# 01_Power.net
KiCad netlist of a schematic drawn in Altium Designer
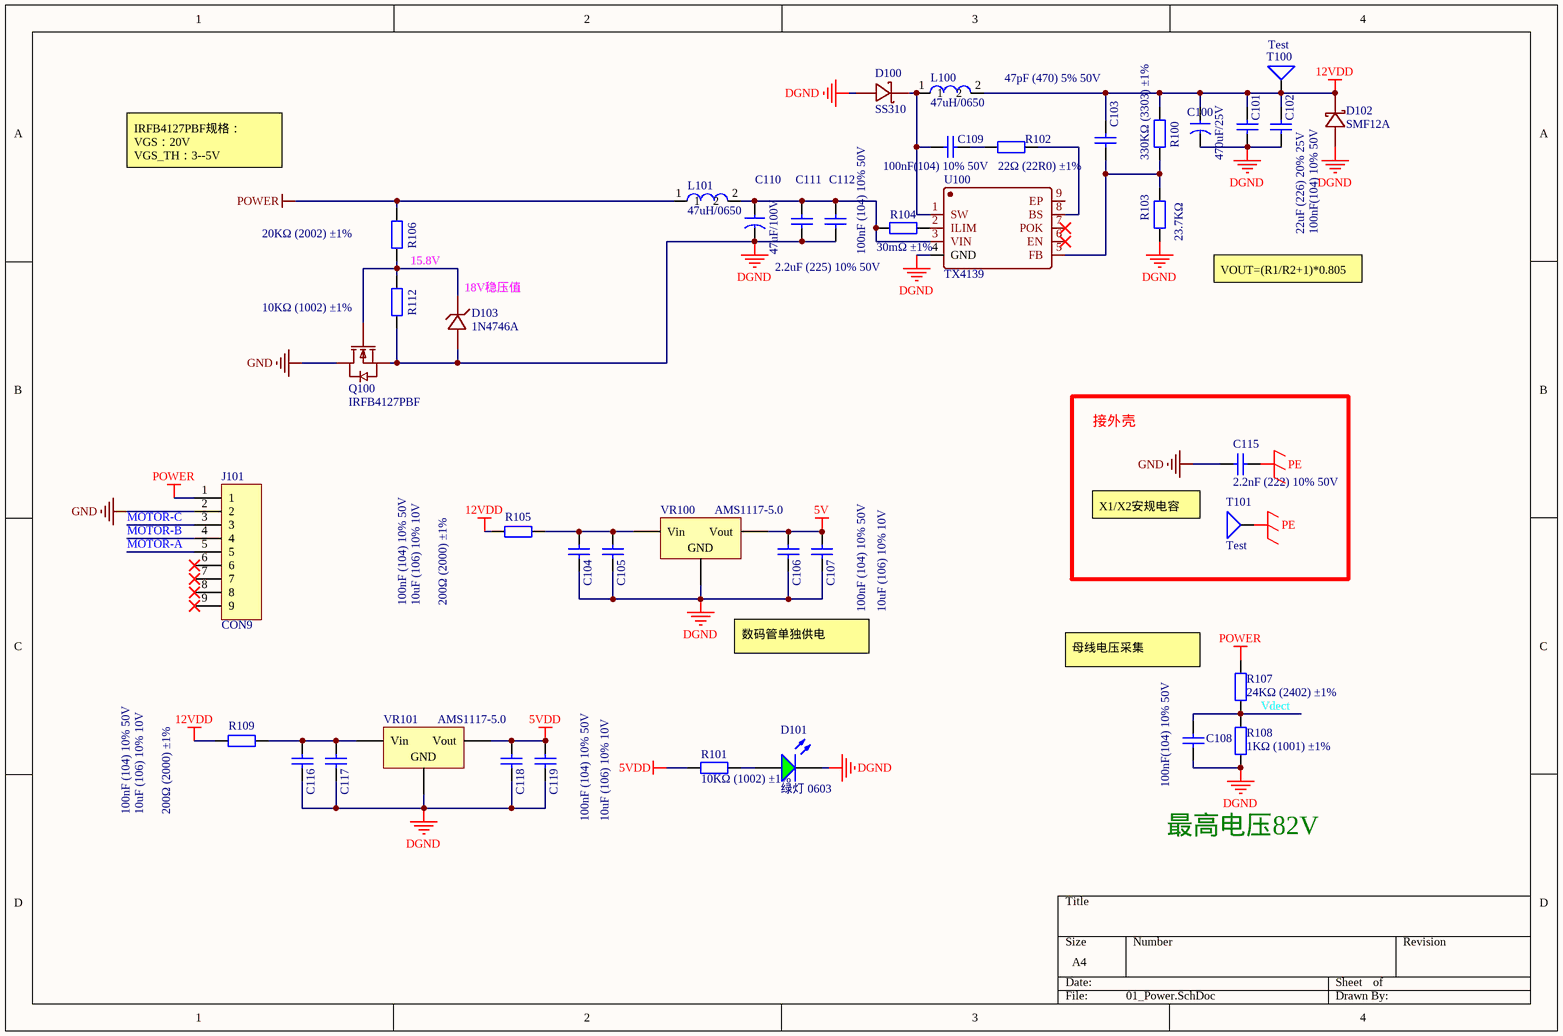
[diagram p0: 01_Power.SchDoc]

(export (version "E")
  (design (tool "Eeschema 10.0.6"))
  (components
    (comp (ref "C100")
      (value "470uF/25V")
      (footprint "47UF/100V")
      (libsource (lib "RayPCB20210502") (part "CapSMT220u_16V"))
    )
    (comp (ref "C101")
      (value "22uF (226) 20% 25V")
      (footprint "0805_C")
      (description "贴片电容")
      (libsource (lib "Miscellaneous Devices LC") (part "0805 22uF (226) 20% 25V"))
    )
    (comp (ref "C102")
      (value "100nF(104) 10% 50V")
      (footprint "0805_C")
      (description "贴片电容")
      (libsource (lib "Miscellaneous Devices LC") (part "0805 100nF(104) 10% 50V"))
    )
    (comp (ref "C103")
      (value "47pF (470) 5% 50V")
      (footprint "0805_C")
      (description "贴片电容")
      (libsource (lib "Miscellaneous Devices LC") (part "0805 47pF (470) 5% 50V"))
    )
    (comp (ref "C104")
      (value "100nF (104) 10% 50V")
      (footprint "0603_C")
      (description "贴片电容")
      (libsource (lib "Miscellaneous Devices LC") (part "0603 100nF (104) 10% 50V"))
    )
    (comp (ref "C105")
      (value "10uF (106) 10% 10V")
      (footprint "0603_C")
      (description "贴片电容")
      (libsource (lib "Miscellaneous Devices LC") (part "0603 10uF (106) 10% 10V"))
    )
    (comp (ref "C106")
      (value "100nF (104) 10% 50V")
      (footprint "0603_C")
      (description "贴片电容")
      (libsource (lib "Miscellaneous Devices LC") (part "0603 100nF (104) 10% 50V"))
    )
    (comp (ref "C107")
      (value "10uF (106) 10% 10V")
      (footprint "0603_C")
      (description "贴片电容")
      (libsource (lib "Miscellaneous Devices LC") (part "0603 10uF (106) 10% 10V"))
    )
    (comp (ref "C108")
      (value "100nF(104) 10% 50V")
      (footprint "0805_C")
      (description "贴片电容")
      (libsource (lib "Miscellaneous Devices LC") (part "0805 100nF(104) 10% 50V"))
    )
    (comp (ref "C109")
      (value "100nF(104) 10% 50V")
      (footprint "0805_C")
      (description "贴片电容")
      (libsource (lib "Miscellaneous Devices LC") (part "0805 100nF(104) 10% 50V"))
    )
    (comp (ref "C110")
      (value "47uF/100V")
      (footprint "47UF/100V")
      (libsource (lib "RayPCB20210502") (part "CapSMT220u_16V"))
    )
    (comp (ref "C111")
      (value "2.2uF (225) 10% 50V")
      (footprint "1206_C")
      (description "贴片电容")
      (libsource (lib "Miscellaneous Devices LC") (part "1206 2.2uF (225) 10% 50V"))
    )
    (comp (ref "C112")
      (value "100nF (104) 10% 50V")
      (footprint "1206_C")
      (description "贴片电容")
      (libsource (lib "Miscellaneous Devices LC") (part "1206 100nF (104) 10% 50V"))
    )
    (comp (ref "C115")
      (value "2.2nF (222) 10% 50V")
      (footprint "X1/Y1 500V")
      (description "贴片电容")
      (libsource (lib "Miscellaneous Devices LC") (part "0603 2.2nF (222) 10% 50V"))
    )
    (comp (ref "C116")
      (value "100nF (104) 10% 50V")
      (footprint "0603_C")
      (description "贴片电容")
      (libsource (lib "Miscellaneous Devices LC") (part "0603 100nF (104) 10% 50V"))
    )
    (comp (ref "C117")
      (value "10uF (106) 10% 10V")
      (footprint "0603_C")
      (description "贴片电容")
      (libsource (lib "Miscellaneous Devices LC") (part "0603 10uF (106) 10% 10V"))
    )
    (comp (ref "C118")
      (value "100nF (104) 10% 50V")
      (footprint "0603_C")
      (description "贴片电容")
      (libsource (lib "Miscellaneous Devices LC") (part "0603 100nF (104) 10% 50V"))
    )
    (comp (ref "C119")
      (value "10uF (106) 10% 10V")
      (footprint "0603_C")
      (description "贴片电容")
      (libsource (lib "Miscellaneous Devices LC") (part "0603 10uF (106) 10% 10V"))
    )
    (comp (ref "D100") (value "SS310") (footprint "SS310") (libsource (lib "Schlibv2") (part "SS310")))
    (comp (ref "D101")
      (value "绿灯 0603")
      (footprint "0603_LED_S1")
      (description "发光二极管")
      (libsource (lib "Miscellaneous Devices LC") (part "0603 绿灯"))
    )
    (comp (ref "D102")
      (value "SMF12A")
      (footprint "SMF12A - duplicate")
      (libsource (lib "RayPCB20210502") (part "SMF12A"))
    )
    (comp (ref "D103") (value "1N4746A") (footprint "1N4746A") (libsource (lib "Schlibv2") (part "1N4746A")))
    (comp (ref "J101")
      (value "CON9")
      (footprint "CON9 9.5mm")
      (libsource (lib "RayPCB20210502") (part "CON9"))
    )
    (comp (ref "L100")
      (value "47uH/0650")
      (footprint "0650_47uH")
      (libsource (lib "RayPCB20210502") (part "Inductor"))
    )
    (comp (ref "L101")
      (value "47uH/0650")
      (footprint "0650_47uH")
      (libsource (lib "RayPCB20210502") (part "Inductor"))
    )
    (comp (ref "Q100")
      (value "IRFB4127PBF")
      (footprint "IRFB4127")
      (libsource (lib "RayPCB20210502") (part "IRFB4127PBF"))
    )
    (comp (ref "R100")
      (value "330KΩ (3303) ±1%")
      (footprint "0805_R")
      (description "贴片电阻")
      (libsource (lib "Miscellaneous Devices LC") (part "0805 330KΩ (3303) 1%"))
    )
    (comp (ref "R101")
      (value "10KΩ (1002) ±1%")
      (footprint "0603_R")
      (description "贴片电阻")
      (libsource (lib "Miscellaneous Devices LC") (part "0603 10KΩ (1002) 1%"))
    )
    (comp (ref "R102")
      (value "22Ω (22R0) ±1%")
      (footprint "0805_R")
      (description "贴片电阻")
      (libsource (lib "") (part "0805 22Ω (22R0) 1%_1"))
    )
    (comp (ref "R103")
      (value "23.7KΩ")
      (footprint "0805_R")
      (description "贴片电阻")
      (libsource (lib "Miscellaneous Devices LC") (part "0805 22Ω (22R0) 1%"))
    )
    (comp (ref "R104")
      (value "30mΩ ±1%")
      (footprint "0603_R")
      (description "贴片电阻")
      (libsource (lib "Miscellaneous Devices LC") (part "0603 100KΩ (1003) 1%"))
    )
    (comp (ref "R105")
      (value "200Ω (2000) ±1%")
      (footprint "1206_R")
      (description "贴片电阻")
      (libsource (lib "Miscellaneous Devices LC") (part "1206 300Ω (3000) 1%"))
    )
    (comp (ref "R106")
      (value "20KΩ (2002) ±1%")
      (footprint "0805_R")
      (description "贴片电阻")
      (libsource (lib "Miscellaneous Devices LC") (part "0805 20KΩ (2002) 1%"))
    )
    (comp (ref "R107")
      (value "24KΩ (2402) ±1%")
      (footprint "1206_R")
      (description "贴片电阻")
      (libsource (lib "Miscellaneous Devices LC") (part "1206 0Ω (0R0) 1%"))
    )
    (comp (ref "R108")
      (value "1KΩ (1001) ±1%")
      (footprint "0805_R")
      (description "贴片电阻")
      (libsource (lib "Miscellaneous Devices LC") (part "0805 1KΩ (1001) 1%"))
    )
    (comp (ref "R109")
      (value "200Ω (2000) ±1%")
      (footprint "1206_R")
      (description "贴片电阻")
      (libsource (lib "Miscellaneous Devices LC") (part "1206 300Ω (3000) 1%"))
    )
    (comp (ref "R112")
      (value "10KΩ (1002) ±1%")
      (footprint "0805_R")
      (description "贴片电阻")
      (libsource (lib "Miscellaneous Devices LC") (part "0805 10KΩ (1002) 1%"))
    )
    (comp (ref "T100")
      (value "Test")
      (footprint "Testpoint")
      (libsource (lib "RayPCB20210502") (part "TestPad"))
    )
    (comp (ref "T101") (value "Test") (footprint "接地螺丝孔") (libsource (lib "RayPCB20210502") (part "TestPad")))
    (comp (ref "U100")
      (value "TX4139")
      (footprint "ESOP8")
      (libsource (lib "RayPCB20210502") (part "TX4139"))
    )
    (comp (ref "VR100")
      (value "AMS1117-5.0")
      (footprint "SOT-223")
      (description "低压差线性稳压(LDO)")
      (libsource (lib "Miscellaneous Devices LC") (part "SOT-223 AMS1117-5.0"))
    )
    (comp (ref "VR101")
      (value "AMS1117-5.0")
      (footprint "SOT-223")
      (description "低压差线性稳压(LDO)")
      (libsource (lib "Miscellaneous Devices LC") (part "SOT-223 AMS1117-5.0"))
    )
  )
  (nets
    (net (code "1") (name "/MOTOR-A") (class "Default")
      (node (ref "J101") (pin "5") (pinfunction "5_5") (pintype "passive"))
    )
    (net (code "2") (name "/MOTOR-B") (class "Default")
      (node (ref "J101") (pin "4") (pinfunction "4_4") (pintype "passive"))
    )
    (net (code "3") (name "/MOTOR-C") (class "Default")
      (node (ref "J101") (pin "3") (pinfunction "3_3") (pintype "passive"))
    )
    (net (code "4") (name "/Vdect") (class "Default")
      (node (ref "C108") (pin "2") (pinfunction "2_2") (pintype "passive"))
      (node (ref "R107") (pin "1") (pinfunction "1_1") (pintype "passive"))
      (node (ref "R108") (pin "2") (pinfunction "2_2") (pintype "passive"))
    )
    (net (code "5") (name "5V") (class "Default")
      (node (ref "C106") (pin "2") (pinfunction "2_2") (pintype "passive"))
      (node (ref "C107") (pin "2") (pinfunction "2_2") (pintype "passive"))
      (node (ref "VR100") (pin "2") (pinfunction "Vout_2") (pintype "passive"))
    )
    (net (code "6") (name "5VDD") (class "Default")
      (node (ref "C118") (pin "2") (pinfunction "2_2") (pintype "passive"))
      (node (ref "C119") (pin "2") (pinfunction "2_2") (pintype "passive"))
      (node (ref "R101") (pin "2") (pinfunction "2_2") (pintype "passive"))
      (node (ref "VR101") (pin "2") (pinfunction "Vout_2") (pintype "passive"))
    )
    (net (code "7") (name "12VDD") (class "Default")
      (node (ref "C100") (pin "1") (pintype "passive"))
      (node (ref "C101") (pin "2") (pinfunction "2_2") (pintype "passive"))
      (node (ref "C102") (pin "2") (pinfunction "2_2") (pintype "passive"))
      (node (ref "C103") (pin "2") (pinfunction "2_2") (pintype "passive"))
      (node (ref "D102") (pin "1") (pinfunction "K_1") (pintype "passive"))
      (node (ref "L100") (pin "2") (pinfunction "2_2") (pintype "passive"))
      (node (ref "R100") (pin "2") (pinfunction "2_2") (pintype "passive"))
      (node (ref "R105") (pin "1") (pinfunction "1_1") (pintype "passive"))
      (node (ref "R109") (pin "1") (pinfunction "1_1") (pintype "passive"))
      (node (ref "T100") (pin "1") (pinfunction "1_1") (pintype "passive"))
    )
    (net (code "8") (name "DGND") (class "Default")
      (node (ref "C100") (pin "2") (pintype "passive"))
      (node (ref "C101") (pin "1") (pinfunction "1_1") (pintype "passive"))
      (node (ref "C102") (pin "1") (pinfunction "1_1") (pintype "passive"))
      (node (ref "C104") (pin "1") (pinfunction "1_1") (pintype "passive"))
      (node (ref "C105") (pin "1") (pinfunction "1_1") (pintype "passive"))
      (node (ref "C106") (pin "1") (pinfunction "1_1") (pintype "passive"))
      (node (ref "C107") (pin "1") (pinfunction "1_1") (pintype "passive"))
      (node (ref "C108") (pin "1") (pinfunction "1_1") (pintype "passive"))
      (node (ref "C110") (pin "2") (pintype "passive"))
      (node (ref "C111") (pin "1") (pinfunction "1_1") (pintype "passive"))
      (node (ref "C112") (pin "1") (pinfunction "1_1") (pintype "passive"))
      (node (ref "C116") (pin "1") (pinfunction "1_1") (pintype "passive"))
      (node (ref "C117") (pin "1") (pinfunction "1_1") (pintype "passive"))
      (node (ref "C118") (pin "1") (pinfunction "1_1") (pintype "passive"))
      (node (ref "C119") (pin "1") (pinfunction "1_1") (pintype "passive"))
      (node (ref "D100") (pin "2") (pinfunction "A_2") (pintype "passive"))
      (node (ref "D101") (pin "K") (pinfunction "K_K") (pintype "passive"))
      (node (ref "D102") (pin "2") (pinfunction "A_2") (pintype "passive"))
      (node (ref "D103") (pin "1") (pinfunction "A_1") (pintype "passive"))
      (node (ref "Q100") (pin "3") (pinfunction "S_3") (pintype "passive"))
      (node (ref "R103") (pin "1") (pinfunction "1_1") (pintype "passive"))
      (node (ref "R108") (pin "1") (pinfunction "1_1") (pintype "passive"))
      (node (ref "R112") (pin "1") (pinfunction "1_1") (pintype "passive"))
      (node (ref "U100") (pin "4") (pinfunction "GND_4") (pintype "passive"))
      (node (ref "VR100") (pin "1") (pinfunction "GND_1") (pintype "passive"))
      (node (ref "VR101") (pin "1") (pinfunction "GND_1") (pintype "passive"))
    )
    (net (code "9") (name "GND") (class "Default")
      (node (ref "C115") (pin "1") (pinfunction "1_1") (pintype "passive"))
      (node (ref "J101") (pin "2") (pinfunction "2_2") (pintype "passive"))
      (node (ref "Q100") (pin "2") (pinfunction "D_2") (pintype "passive"))
    )
    (net (code "10") (name "Net-(C109-Pad2)") (class "Default")
      (node (ref "C109") (pin "2") (pinfunction "2_2") (pintype "passive"))
      (node (ref "R102") (pin "1") (pinfunction "1_1") (pintype "passive"))
    )
    (net (code "11") (name "Net-(D100-K)") (class "Default")
      (node (ref "C109") (pin "1") (pinfunction "1_1") (pintype "passive"))
      (node (ref "D100") (pin "1") (pinfunction "K_1") (pintype "passive"))
      (node (ref "L100") (pin "1") (pinfunction "1_1") (pintype "passive"))
      (node (ref "U100") (pin "1") (pinfunction "SW_1") (pintype "passive"))
    )
    (net (code "12") (name "Net-(D101-PadA)") (class "Default")
      (node (ref "D101") (pin "A") (pinfunction "A_A") (pintype "passive"))
      (node (ref "R101") (pin "1") (pinfunction "1_1") (pintype "passive"))
    )
    (net (code "13") (name "Net-(D103-K)") (class "Default")
      (node (ref "D103") (pin "2") (pinfunction "K_2") (pintype "passive"))
      (node (ref "Q100") (pin "1") (pinfunction "G_1") (pintype "passive"))
      (node (ref "R106") (pin "1") (pinfunction "1_1") (pintype "passive"))
      (node (ref "R112") (pin "2") (pinfunction "2_2") (pintype "passive"))
    )
    (net (code "14") (name "Net-(U100-BS)") (class "Default")
      (node (ref "R102") (pin "2") (pinfunction "2_2") (pintype "passive"))
      (node (ref "U100") (pin "8") (pinfunction "BS_8") (pintype "passive"))
    )
    (net (code "15") (name "Net-(U100-FB)") (class "Default")
      (node (ref "C103") (pin "1") (pinfunction "1_1") (pintype "passive"))
      (node (ref "R100") (pin "1") (pinfunction "1_1") (pintype "passive"))
      (node (ref "R103") (pin "2") (pinfunction "2_2") (pintype "passive"))
      (node (ref "U100") (pin "5") (pinfunction "FB_5") (pintype "passive"))
    )
    (net (code "16") (name "Net-(U100-ILIM)") (class "Default")
      (node (ref "R104") (pin "1") (pinfunction "1_1") (pintype "passive"))
      (node (ref "U100") (pin "2") (pinfunction "ILIM_2") (pintype "passive"))
    )
    (net (code "17") (name "Net-(U100-VIN)") (class "Default")
      (node (ref "C110") (pin "1") (pintype "passive"))
      (node (ref "C111") (pin "2") (pinfunction "2_2") (pintype "passive"))
      (node (ref "C112") (pin "2") (pinfunction "2_2") (pintype "passive"))
      (node (ref "L101") (pin "2") (pinfunction "2_2") (pintype "passive"))
      (node (ref "R104") (pin "2") (pinfunction "2_2") (pintype "passive"))
      (node (ref "U100") (pin "3") (pinfunction "VIN_3") (pintype "passive"))
    )
    (net (code "18") (name "Net-(VR100-Vin)") (class "Default")
      (node (ref "C104") (pin "2") (pinfunction "2_2") (pintype "passive"))
      (node (ref "C105") (pin "2") (pinfunction "2_2") (pintype "passive"))
      (node (ref "R105") (pin "2") (pinfunction "2_2") (pintype "passive"))
      (node (ref "VR100") (pin "3") (pinfunction "Vin_3") (pintype "passive"))
    )
    (net (code "19") (name "Net-(VR101-Vin)") (class "Default")
      (node (ref "C116") (pin "2") (pinfunction "2_2") (pintype "passive"))
      (node (ref "C117") (pin "2") (pinfunction "2_2") (pintype "passive"))
      (node (ref "R109") (pin "2") (pinfunction "2_2") (pintype "passive"))
      (node (ref "VR101") (pin "3") (pinfunction "Vin_3") (pintype "passive"))
    )
    (net (code "20") (name "PE") (class "Default")
      (node (ref "C115") (pin "2") (pinfunction "2_2") (pintype "passive"))
      (node (ref "T101") (pin "1") (pinfunction "1_1") (pintype "passive"))
    )
    (net (code "21") (name "POWER") (class "Default")
      (node (ref "J101") (pin "1") (pinfunction "1_1") (pintype "passive"))
      (node (ref "L101") (pin "1") (pinfunction "1_1") (pintype "passive"))
      (node (ref "R106") (pin "2") (pinfunction "2_2") (pintype "passive"))
      (node (ref "R107") (pin "2") (pinfunction "2_2") (pintype "passive"))
    )
    (net (code "22") (name "unconnected-(J101-Pad6)") (class "Default")
      (node (ref "J101") (pin "6") (pinfunction "6_6") (pintype "passive+no_connect"))
    )
    (net (code "23") (name "unconnected-(J101-Pad7)") (class "Default")
      (node (ref "J101") (pin "7") (pinfunction "7_7") (pintype "passive+no_connect"))
    )
    (net (code "24") (name "unconnected-(J101-Pad8)") (class "Default")
      (node (ref "J101") (pin "8") (pinfunction "8_8") (pintype "passive+no_connect"))
    )
    (net (code "25") (name "unconnected-(J101-Pad9)") (class "Default")
      (node (ref "J101") (pin "9") (pinfunction "9_9") (pintype "passive+no_connect"))
    )
    (net (code "26") (name "unconnected-(U100-EN-Pad6)") (class "Default")
      (node (ref "U100") (pin "6") (pinfunction "EN_6") (pintype "passive+no_connect"))
    )
    (net (code "27") (name "unconnected-(U100-EP-Pad9)") (class "Default")
      (node (ref "U100") (pin "9") (pinfunction "EP_9") (pintype "passive"))
    )
    (net (code "28") (name "unconnected-(U100-POK-Pad7)") (class "Default")
      (node (ref "U100") (pin "7") (pinfunction "POK_7") (pintype "passive+no_connect"))
    )
  )
)
